# 5vBuckV2_1.net
KiCad netlist of a schematic drawn in EAGLE
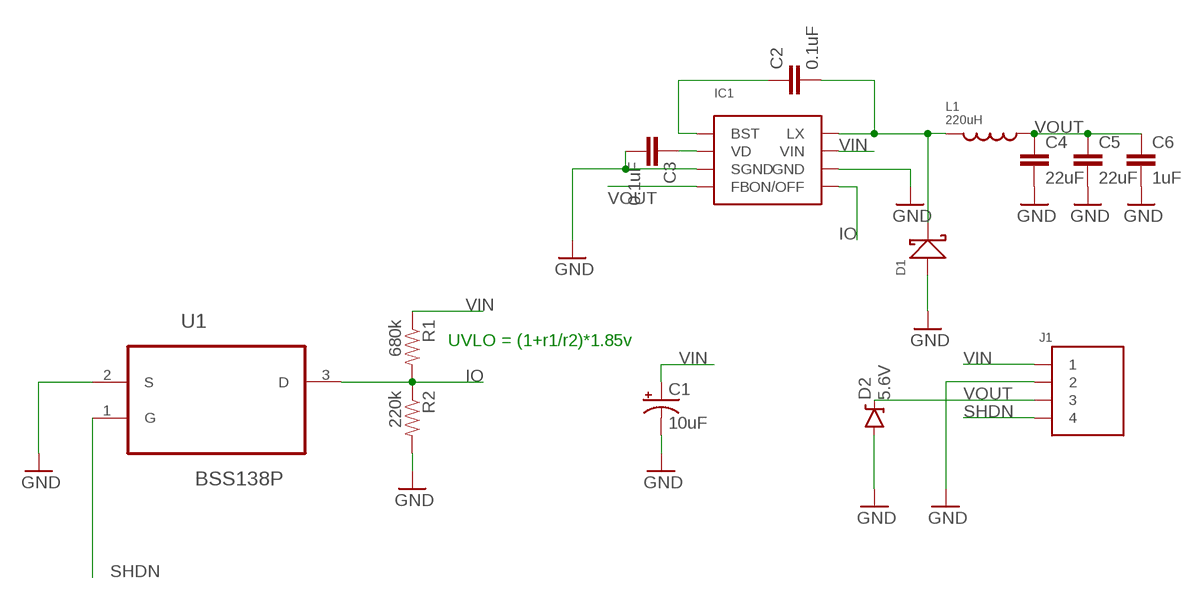
[diagram p0: schematic, sheet 1]

(export (version "E")
  (design (tool "Eeschema 10.0.6"))
  (components
    (comp (ref "C1")
      (value "10uF")
      (footprint "eagle-import:NIPPON_F80")
      (libsource (lib "eagle-import") (part "CAP_POLF80"))
    )
    (comp (ref "C2")
      (value "0.1uF")
      (footprint "eagle-import:0805-CAP")
      (libsource (lib "eagle-import") (part "0.33UF-50V-10%(0805)"))
    )
    (comp (ref "C3")
      (value "0.1uF")
      (footprint "eagle-import:0805-CAP")
      (libsource (lib "eagle-import") (part "0.33UF-50V-10%(0805)"))
    )
    (comp (ref "C4")
      (value "22uF")
      (footprint "eagle-import:0805-CAP")
      (libsource (lib "eagle-import") (part "0.33UF-50V-10%(0805)"))
    )
    (comp (ref "C5")
      (value "22uF")
      (footprint "eagle-import:0805-CAP")
      (libsource (lib "eagle-import") (part "0.33UF-50V-10%(0805)"))
    )
    (comp (ref "C6")
      (value "1uF")
      (footprint "eagle-import:0805-CAP")
      (libsource (lib "eagle-import") (part "0.33UF-50V-10%(0805)"))
    )
    (comp (ref "D1")
      (value "DIODE_SCHOTTKYSOD-123")
      (footprint "eagle-import:SOD-123")
      (libsource (lib "eagle-import") (part "DIODE_SCHOTTKYSOD-123"))
    )
    (comp (ref "D2")
      (value "5.6V")
      (footprint "eagle-import:SOD-323")
      (libsource (lib "eagle-import") (part "DIODE-ZENER5.6V"))
    )
    (comp (ref "IC1")
      (value "M5033")
      (footprint "eagle-import:SOIC-8")
      (libsource (lib "eagle-import") (part "M5033"))
    )
    (comp (ref "J1")
      (value "CONNECTOR_4PIN")
      (footprint "eagle-import:4PIN_.1'")
      (libsource (lib "eagle-import") (part "CONNECTOR_4PIN"))
    )
    (comp (ref "L1")
      (value "220uH")
      (footprint "eagle-import:6X6MM_IND")
      (libsource (lib "eagle-import") (part "CHIP_IND1"))
    )
    (comp (ref "R1")
      (value "680k")
      (footprint "eagle-import:0805")
      (libsource (lib "eagle-import") (part "0.22OHM-1/4W-1%(0805)"))
    )
    (comp (ref "R2")
      (value "220k")
      (footprint "eagle-import:0805")
      (libsource (lib "eagle-import") (part "0.22OHM-1/4W-1%(0805)"))
    )
    (comp (ref "U1")
      (value "BSS138P")
      (footprint "eagle-import:SOT95P230X110-3N")
      (libsource (lib "eagle-import") (part "BSS138P"))
    )
  )
  (nets
    (net (code "1") (name "/IO") (class "Default")
      (node (ref "IC1") (pin "P$5") (pinfunction "ON/OFF_P$5") (pintype "bidirectional"))
      (node (ref "R1") (pin "2") (pinfunction "2_2") (pintype "passive"))
      (node (ref "R2") (pin "1") (pinfunction "1_1") (pintype "passive"))
      (node (ref "U1") (pin "3") (pinfunction "D_3") (pintype "passive"))
    )
    (net (code "2") (name "/SHDN") (class "Default")
      (node (ref "J1") (pin "P$4") (pinfunction "4_P$4") (pintype "bidirectional"))
      (node (ref "U1") (pin "1") (pinfunction "G_1") (pintype "passive"))
    )
    (net (code "3") (name "/VIN") (class "Default")
      (node (ref "C1") (pin "+") (pinfunction "+_+") (pintype "passive"))
      (node (ref "IC1") (pin "P$7") (pinfunction "VIN_P$7") (pintype "bidirectional"))
      (node (ref "J1") (pin "P$1") (pinfunction "1_P$1") (pintype "bidirectional"))
      (node (ref "R1") (pin "1") (pinfunction "1_1") (pintype "passive"))
    )
    (net (code "4") (name "/VOUT") (class "Default")
      (node (ref "C4") (pin "1") (pinfunction "1_1") (pintype "passive"))
      (node (ref "C5") (pin "1") (pinfunction "1_1") (pintype "passive"))
      (node (ref "C6") (pin "1") (pinfunction "1_1") (pintype "passive"))
      (node (ref "D2") (pin "C") (pinfunction "C_C") (pintype "passive"))
      (node (ref "IC1") (pin "P$4") (pinfunction "FB_P$4") (pintype "bidirectional"))
      (node (ref "J1") (pin "P$3") (pinfunction "3_P$3") (pintype "bidirectional"))
      (node (ref "L1") (pin "P$2") (pinfunction "P$2_P$2") (pintype "bidirectional"))
    )
    (net (code "5") (name "GND") (class "Default")
      (node (ref "C1") (pin "-") (pinfunction "-_-") (pintype "passive"))
      (node (ref "C3") (pin "2") (pinfunction "2_2") (pintype "passive"))
      (node (ref "C4") (pin "2") (pinfunction "2_2") (pintype "passive"))
      (node (ref "C5") (pin "2") (pinfunction "2_2") (pintype "passive"))
      (node (ref "C6") (pin "2") (pinfunction "2_2") (pintype "passive"))
      (node (ref "D1") (pin "ANODE") (pinfunction "ANODE_ANODE") (pintype "bidirectional"))
      (node (ref "D2") (pin "A") (pinfunction "A_A") (pintype "passive"))
      (node (ref "IC1") (pin "P$3") (pinfunction "SGND_P$3") (pintype "bidirectional"))
      (node (ref "IC1") (pin "P$6") (pinfunction "GND_P$6") (pintype "bidirectional"))
      (node (ref "J1") (pin "P$2") (pinfunction "2_P$2") (pintype "bidirectional"))
      (node (ref "R2") (pin "2") (pinfunction "2_2") (pintype "passive"))
      (node (ref "U1") (pin "2") (pinfunction "S_2") (pintype "passive"))
    )
    (net (code "6") (name "Net-(IC1-BST)") (class "Default")
      (node (ref "C2") (pin "1") (pinfunction "1_1") (pintype "passive"))
      (node (ref "IC1") (pin "P$1") (pinfunction "BST_P$1") (pintype "bidirectional"))
    )
    (net (code "7") (name "Net-(IC1-LX)") (class "Default")
      (node (ref "C2") (pin "2") (pinfunction "2_2") (pintype "passive"))
      (node (ref "D1") (pin "CATHODE") (pinfunction "CATHODE_CATHODE") (pintype "bidirectional"))
      (node (ref "IC1") (pin "P$8") (pinfunction "LX_P$8") (pintype "bidirectional"))
      (node (ref "L1") (pin "P$1") (pinfunction "P$1_P$1") (pintype "bidirectional"))
    )
    (net (code "8") (name "Net-(IC1-VD)") (class "Default")
      (node (ref "C3") (pin "1") (pinfunction "1_1") (pintype "passive"))
      (node (ref "IC1") (pin "P$2") (pinfunction "VD_P$2") (pintype "bidirectional"))
    )
  )
)
